# integratedBertha.net
KiCad netlist of a schematic drawn in EAGLE
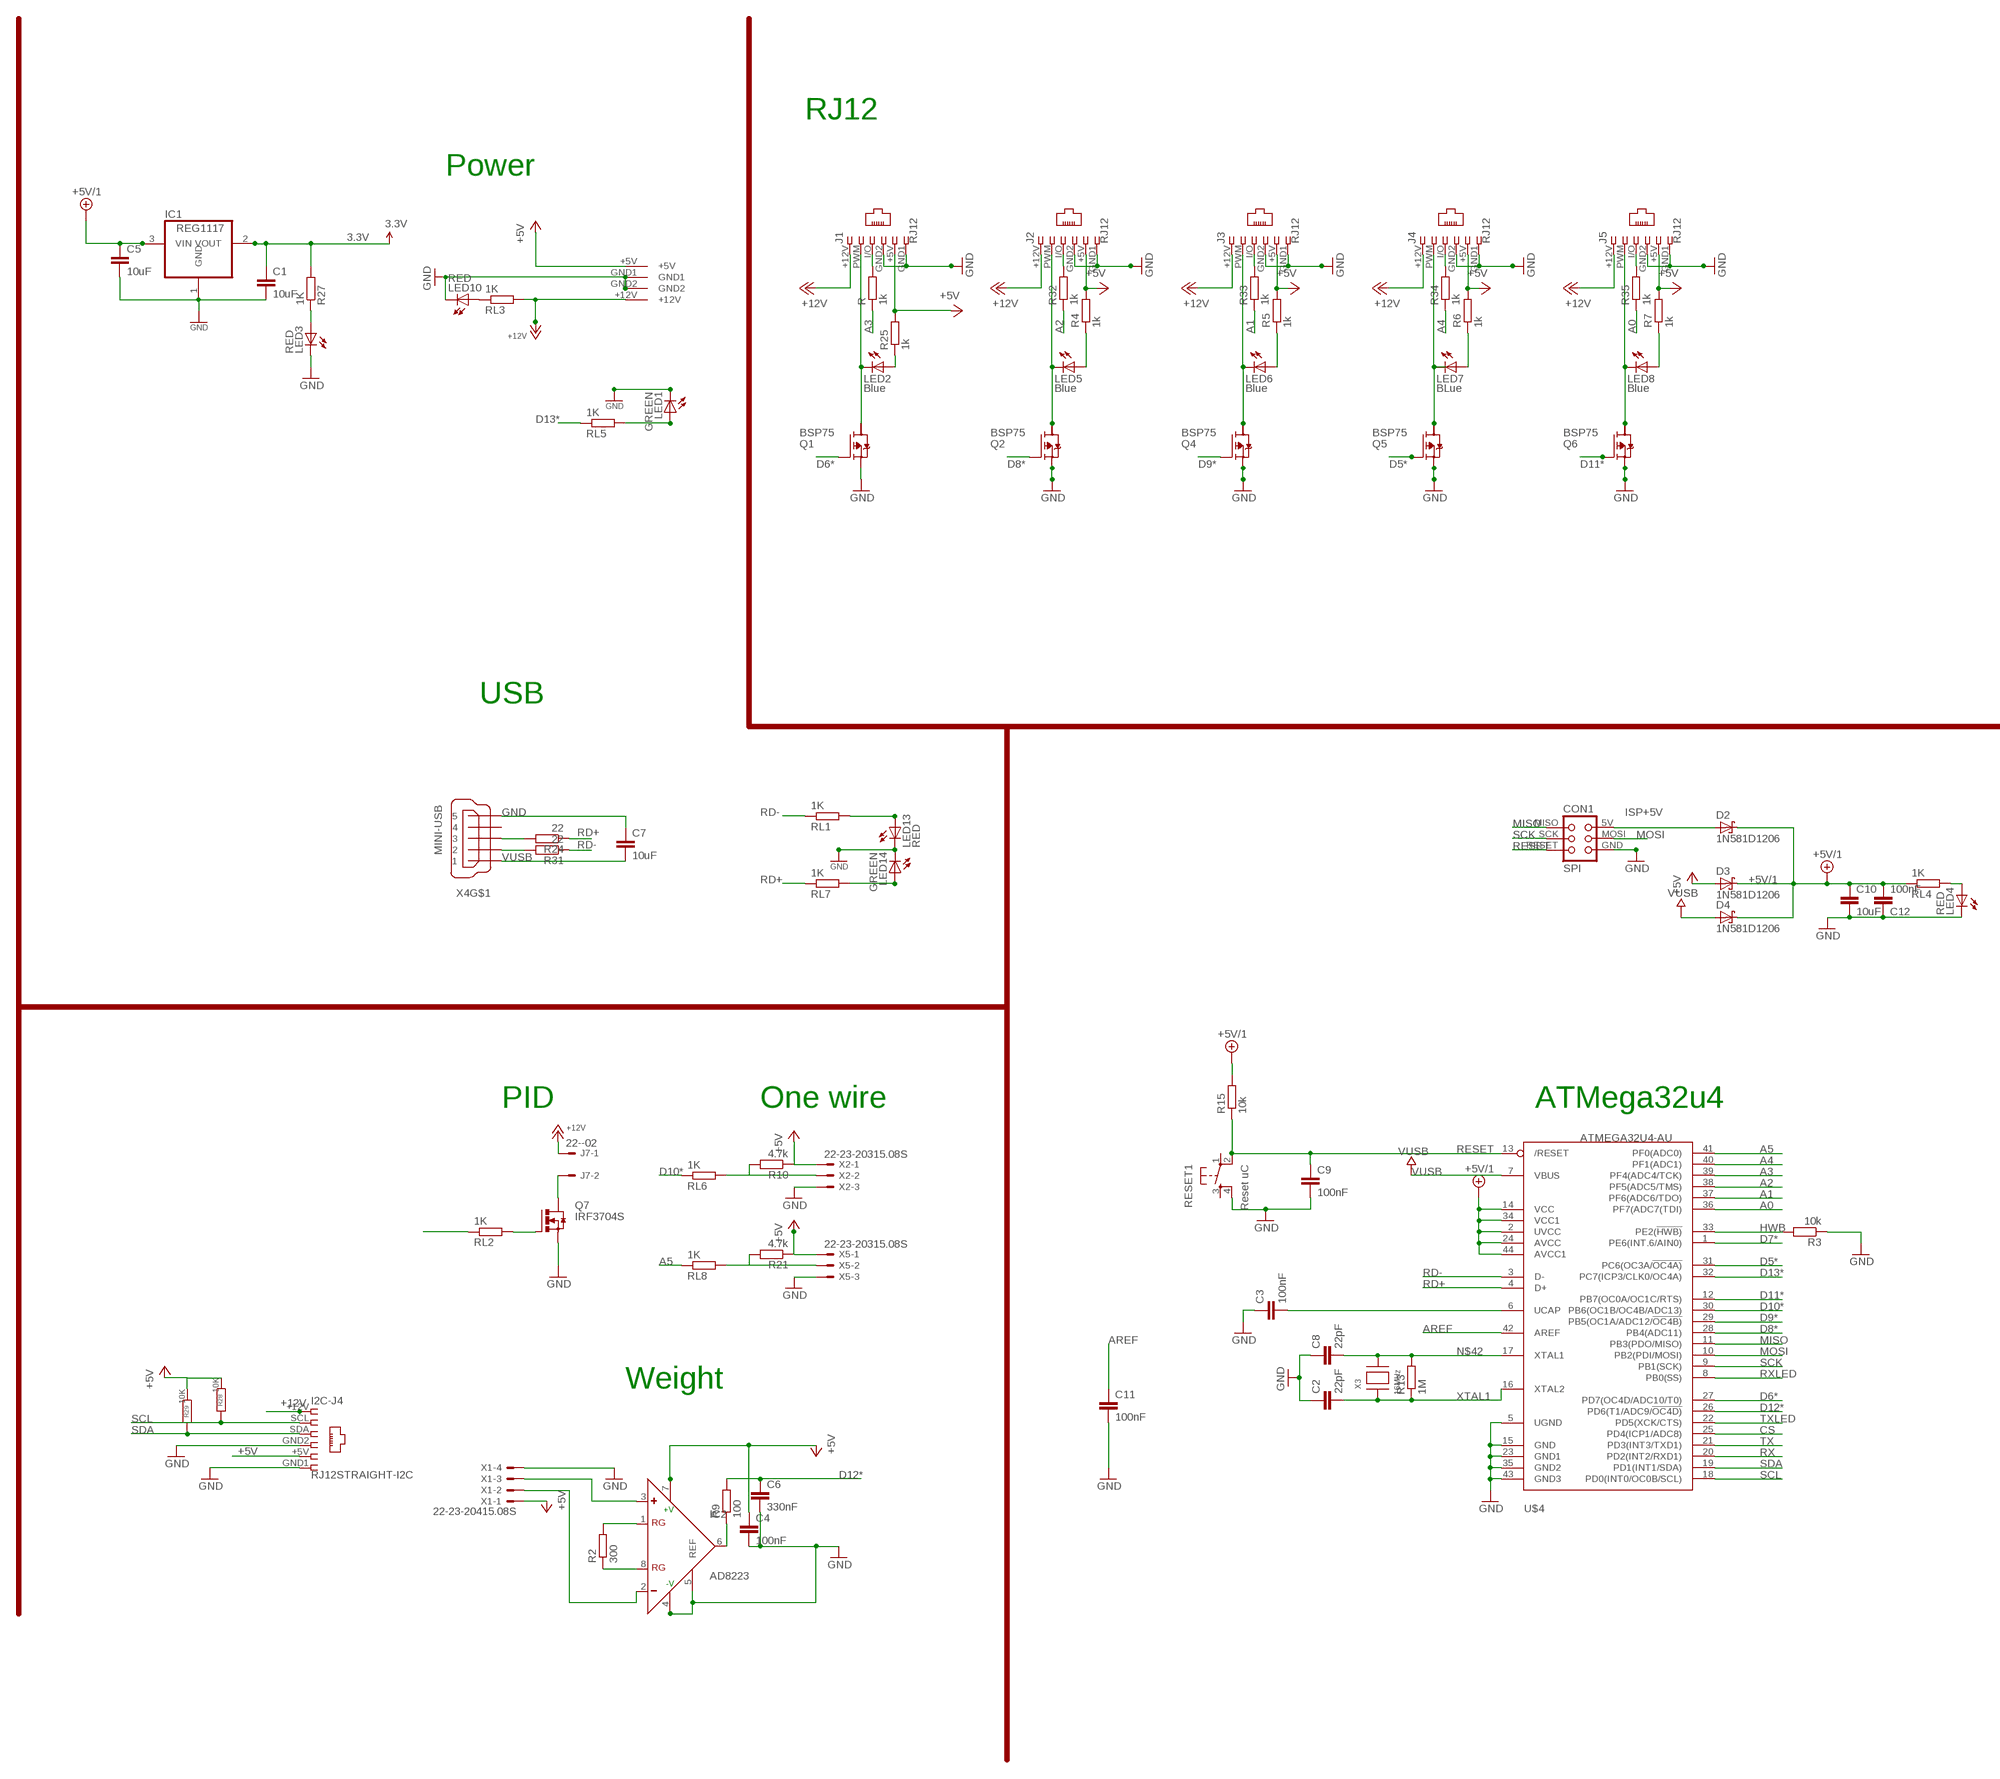
[diagram p0: schematic, sheet 1, part 1 of 2]
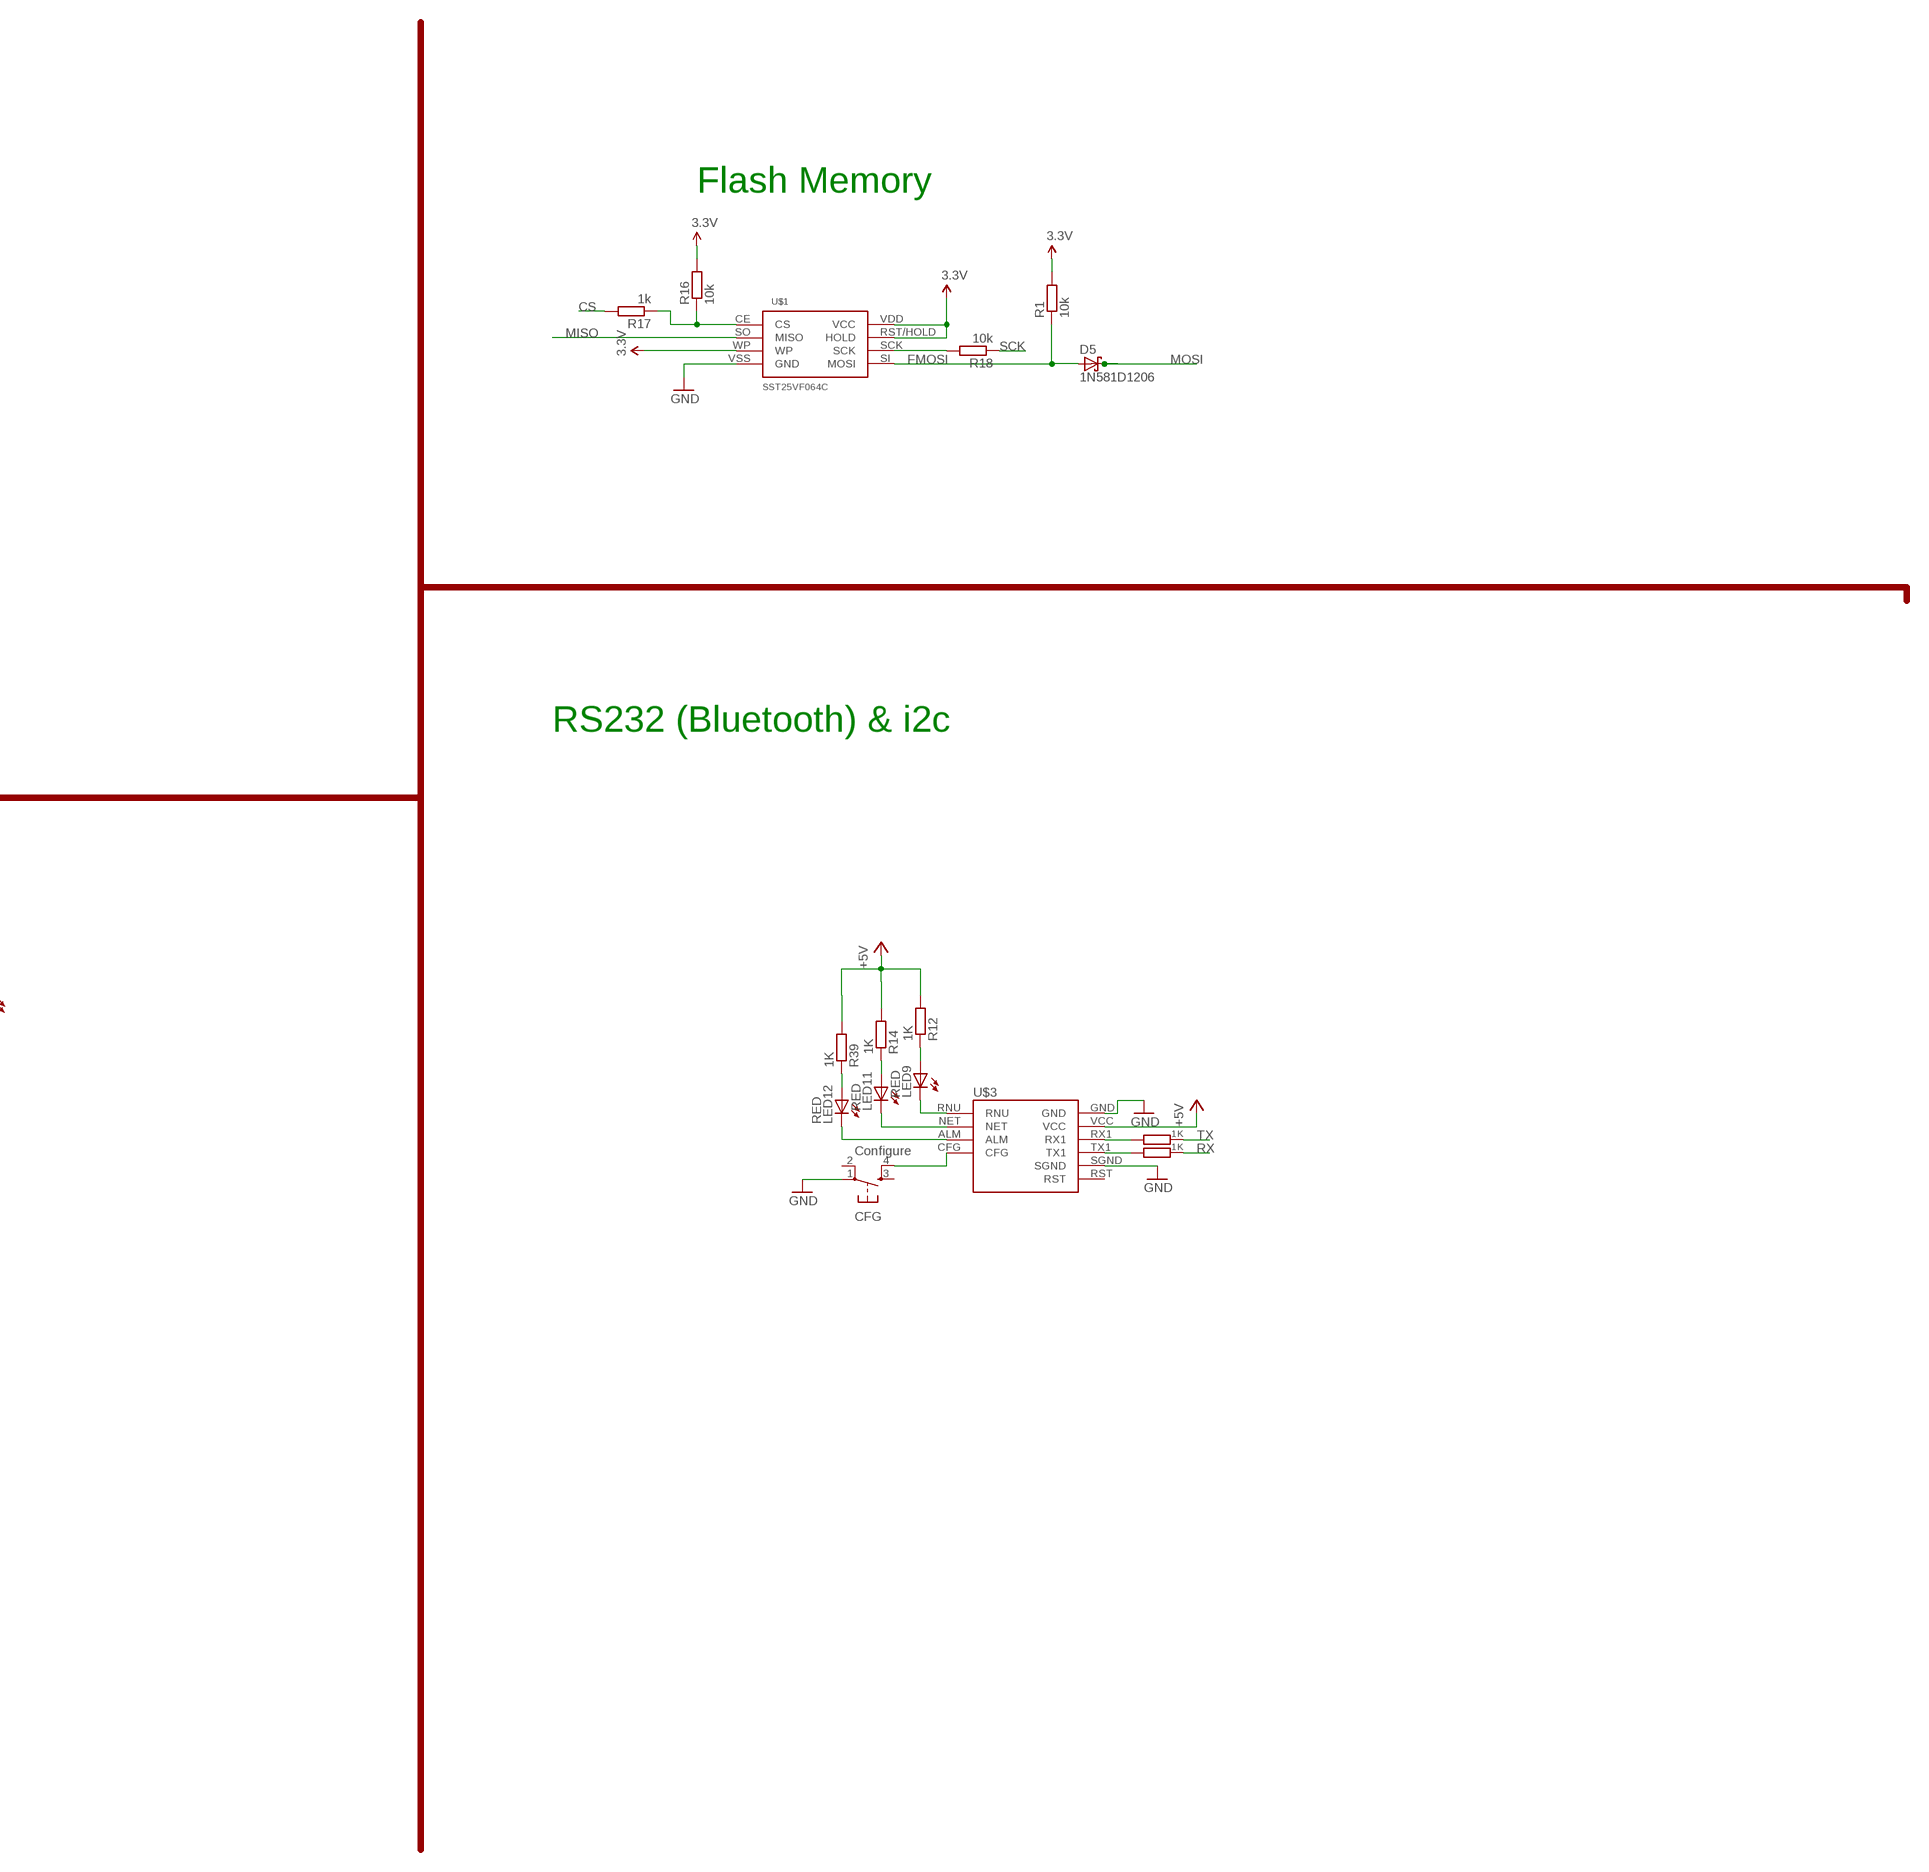
[diagram p1: schematic, sheet 1, part 2 of 2]

(export (version "E")
  (design (tool "Eeschema 10.0.6"))
  (components
    (comp (ref "C1")
      (value "10uF")
      (footprint "eagle-import:C1206")
      (libsource (lib "eagle-import") (part "C-EUC1206"))
    )
    (comp (ref "C2")
      (value "22pF")
      (footprint "eagle-import:C1206")
      (libsource (lib "eagle-import") (part "C-EUC1206"))
    )
    (comp (ref "C3")
      (value "100nF")
      (footprint "eagle-import:C1206")
      (libsource (lib "eagle-import") (part "C-EUC1206"))
    )
    (comp (ref "C4")
      (value "100nF")
      (footprint "eagle-import:C1206")
      (libsource (lib "eagle-import") (part "C-EUC1206"))
    )
    (comp (ref "C5")
      (value "10uF")
      (footprint "eagle-import:C1206")
      (libsource (lib "eagle-import") (part "C-EUC1206"))
    )
    (comp (ref "C6")
      (value "330nF")
      (footprint "eagle-import:C1206")
      (libsource (lib "eagle-import") (part "C-EUC1206"))
    )
    (comp (ref "C7")
      (value "10uF")
      (footprint "eagle-import:C1206")
      (libsource (lib "eagle-import") (part "C-EUC1206"))
    )
    (comp (ref "C8")
      (value "22pF")
      (footprint "eagle-import:C1206")
      (libsource (lib "eagle-import") (part "C-EUC1206"))
    )
    (comp (ref "C9")
      (value "100nF")
      (footprint "eagle-import:C1206")
      (libsource (lib "eagle-import") (part "C-EUC1206"))
    )
    (comp (ref "C10")
      (value "10uF")
      (footprint "eagle-import:C1206")
      (libsource (lib "eagle-import") (part "C-EUC1206"))
    )
    (comp (ref "C11")
      (value "100nF")
      (footprint "eagle-import:C1206")
      (libsource (lib "eagle-import") (part "C-EUC1206"))
    )
    (comp (ref "C12")
      (value "100nF")
      (footprint "eagle-import:C1206")
      (libsource (lib "eagle-import") (part "C-EUC1206"))
    )
    (comp (ref "CFG")
      (value "Configure")
      (footprint "eagle-import:TACTILE_SWITCH_SMD")
      (libsource (lib "eagle-import") (part "TAC_SWITCHSMD"))
    )
    (comp (ref "CON1")
      (value "SPI")
      (footprint "eagle-import:TC2030-MCP-NL")
      (libsource (lib "eagle-import") (part "TINYISPT"))
    )
    (comp (ref "D2")
      (value "1N581D1206")
      (footprint "eagle-import:LED-1206")
      (libsource (lib "eagle-import") (part "1N581D1206"))
    )
    (comp (ref "D3")
      (value "1N581D1206")
      (footprint "eagle-import:LED-1206")
      (libsource (lib "eagle-import") (part "1N581D1206"))
    )
    (comp (ref "D4")
      (value "1N581D1206")
      (footprint "eagle-import:LED-1206")
      (libsource (lib "eagle-import") (part "1N581D1206"))
    )
    (comp (ref "D5")
      (value "1N581D1206")
      (footprint "eagle-import:LED-1206")
      (libsource (lib "eagle-import") (part "1N581D1206"))
    )
    (comp (ref "I2C-J4")
      (value "RJ12STRAIGHT-I2C")
      (footprint "eagle-import:RJ12-STRAIGHT-I2C")
      (libsource (lib "eagle-import") (part "RJ12STRAIGHT-I2C"))
    )
    (comp (ref "IC1")
      (value "REG1117")
      (footprint "eagle-import:SOT223")
      (libsource (lib "eagle-import") (part "REG1117"))
    )
    (comp (ref "IC2")
      (value "AD8223")
      (footprint "eagle-import:SO8")
      (fields (field (name "MPN") "AD620AR"))
      (libsource (lib "eagle-import") (part "AD620R"))
    )
    (comp (ref "J1")
      (value "RJ12")
      (footprint "eagle-import:RJ12-STRAIGHT")
      (libsource (lib "eagle-import") (part "RJ12STRAIGHT"))
    )
    (comp (ref "J2")
      (value "RJ12")
      (footprint "eagle-import:RJ12-STRAIGHT")
      (libsource (lib "eagle-import") (part "RJ12STRAIGHT"))
    )
    (comp (ref "J3")
      (value "RJ12")
      (footprint "eagle-import:RJ12-STRAIGHT")
      (libsource (lib "eagle-import") (part "RJ12STRAIGHT"))
    )
    (comp (ref "J4")
      (value "RJ12")
      (footprint "eagle-import:RJ12-STRAIGHT")
      (libsource (lib "eagle-import") (part "RJ12STRAIGHT"))
    )
    (comp (ref "J5")
      (value "RJ12")
      (footprint "eagle-import:RJ12-STRAIGHT")
      (libsource (lib "eagle-import") (part "RJ12STRAIGHT"))
    )
    (comp (ref "J7")
      (value "22--02")
      (footprint "eagle-import:2-PIN-5.08S")
      (libsource (lib "eagle-import") (part "22-?-02"))
    )
    (comp (ref "LED1")
      (value "GREEN")
      (footprint "eagle-import:CHIPLED_1206")
      (libsource (lib "eagle-import") (part "LEDCHIPLED_1206"))
    )
    (comp (ref "LED2")
      (value "Blue")
      (footprint "eagle-import:CHIPLED_1206")
      (libsource (lib "eagle-import") (part "LEDCHIPLED_1206"))
    )
    (comp (ref "LED3")
      (value "RED")
      (footprint "eagle-import:CHIPLED_1206")
      (libsource (lib "eagle-import") (part "LEDCHIPLED_1206"))
    )
    (comp (ref "LED4")
      (value "RED")
      (footprint "eagle-import:CHIPLED_1206")
      (libsource (lib "eagle-import") (part "LEDCHIPLED_1206"))
    )
    (comp (ref "LED5")
      (value "Blue")
      (footprint "eagle-import:CHIPLED_1206")
      (libsource (lib "eagle-import") (part "LEDCHIPLED_1206"))
    )
    (comp (ref "LED6")
      (value "Blue")
      (footprint "eagle-import:CHIPLED_1206")
      (libsource (lib "eagle-import") (part "LEDCHIPLED_1206"))
    )
    (comp (ref "LED7")
      (value "BLue")
      (footprint "eagle-import:CHIPLED_1206")
      (libsource (lib "eagle-import") (part "LEDCHIPLED_1206"))
    )
    (comp (ref "LED8")
      (value "Blue")
      (footprint "eagle-import:CHIPLED_1206")
      (libsource (lib "eagle-import") (part "LEDCHIPLED_1206"))
    )
    (comp (ref "LED9")
      (value "RED")
      (footprint "eagle-import:CHIPLED_1206")
      (libsource (lib "eagle-import") (part "LEDCHIPLED_1206"))
    )
    (comp (ref "LED10")
      (value "RED")
      (footprint "eagle-import:CHIPLED_1206")
      (libsource (lib "eagle-import") (part "LEDCHIPLED_1206"))
    )
    (comp (ref "LED11")
      (value "RED")
      (footprint "eagle-import:CHIPLED_1206")
      (libsource (lib "eagle-import") (part "LEDCHIPLED_1206"))
    )
    (comp (ref "LED12")
      (value "RED")
      (footprint "eagle-import:CHIPLED_1206")
      (libsource (lib "eagle-import") (part "LEDCHIPLED_1206"))
    )
    (comp (ref "LED13")
      (value "RED")
      (footprint "eagle-import:CHIPLED_1206")
      (libsource (lib "eagle-import") (part "LEDCHIPLED_1206"))
    )
    (comp (ref "LED14")
      (value "GREEN")
      (footprint "eagle-import:CHIPLED_1206")
      (libsource (lib "eagle-import") (part "LEDCHIPLED_1206"))
    )
    (comp (ref "Q1")
      (value "BSP75")
      (footprint "eagle-import:PG-SOT-223")
      (libsource (lib "eagle-import") (part "BSP613P"))
    )
    (comp (ref "Q2")
      (value "BSP75")
      (footprint "eagle-import:PG-SOT-223")
      (libsource (lib "eagle-import") (part "BSP613P"))
    )
    (comp (ref "Q4")
      (value "BSP75")
      (footprint "eagle-import:PG-SOT-223")
      (libsource (lib "eagle-import") (part "BSP613P"))
    )
    (comp (ref "Q5")
      (value "BSP75")
      (footprint "eagle-import:PG-SOT-223")
      (libsource (lib "eagle-import") (part "BSP613P"))
    )
    (comp (ref "Q6")
      (value "BSP75")
      (footprint "eagle-import:PG-SOT-223")
      (libsource (lib "eagle-import") (part "BSP613P"))
    )
    (comp (ref "Q7")
      (value "IRF3704S")
      (footprint "eagle-import:D2PACK")
      (libsource (lib "eagle-import") (part "IRF3704S"))
    )
    (comp (ref "R")
      (value "1k")
      (footprint "eagle-import:R0805")
      (libsource (lib "eagle-import") (part "R-EU_R0805"))
    )
    (comp (ref "R1")
      (value "10k")
      (footprint "eagle-import:R0805")
      (libsource (lib "eagle-import") (part "R-EU_R0805"))
    )
    (comp (ref "R2")
      (value "300")
      (footprint "eagle-import:R1206")
      (libsource (lib "eagle-import") (part "resistor_R-EU_R1206"))
    )
    (comp (ref "R3")
      (value "10k")
      (footprint "eagle-import:M0805")
      (libsource (lib "eagle-import") (part "resistor_R-EU_M0805"))
    )
    (comp (ref "R4")
      (value "1k")
      (footprint "eagle-import:R0805")
      (libsource (lib "eagle-import") (part "R-EU_R0805"))
    )
    (comp (ref "R5")
      (value "1k")
      (footprint "eagle-import:R0805")
      (libsource (lib "eagle-import") (part "R-EU_R0805"))
    )
    (comp (ref "R6")
      (value "1k")
      (footprint "eagle-import:R0805")
      (libsource (lib "eagle-import") (part "R-EU_R0805"))
    )
    (comp (ref "R7")
      (value "1k")
      (footprint "eagle-import:R0805")
      (libsource (lib "eagle-import") (part "R-EU_R0805"))
    )
    (comp (ref "R8")
      (value "1K")
      (footprint "eagle-import:R0805")
      (libsource (lib "eagle-import") (part "R-EU_R0805"))
    )
    (comp (ref "R9")
      (value "100")
      (footprint "eagle-import:R1206")
      (libsource (lib "eagle-import") (part "resistor_R-EU_R1206"))
    )
    (comp (ref "R10")
      (value "4.7k")
      (footprint "eagle-import:R1206")
      (libsource (lib "eagle-import") (part "resistor_R-EU_R1206"))
    )
    (comp (ref "R11")
      (value "1K")
      (footprint "eagle-import:R0805")
      (libsource (lib "eagle-import") (part "R-EU_R0805"))
    )
    (comp (ref "R12")
      (value "1K")
      (footprint "eagle-import:R0805")
      (libsource (lib "eagle-import") (part "R-EU_R0805"))
    )
    (comp (ref "R13")
      (value "1M")
      (footprint "eagle-import:R1206")
      (libsource (lib "eagle-import") (part "R-EU_R1206"))
    )
    (comp (ref "R14")
      (value "1K")
      (footprint "eagle-import:R0805")
      (libsource (lib "eagle-import") (part "R-EU_R0805"))
    )
    (comp (ref "R15")
      (value "10k")
      (footprint "eagle-import:M0805")
      (libsource (lib "eagle-import") (part "resistor_R-EU_M0805"))
    )
    (comp (ref "R16")
      (value "10k")
      (footprint "eagle-import:R0805")
      (libsource (lib "eagle-import") (part "R-EU_R0805"))
    )
    (comp (ref "R17")
      (value "1k")
      (footprint "eagle-import:R0805")
      (libsource (lib "eagle-import") (part "R-EU_R0805"))
    )
    (comp (ref "R18")
      (value "10k")
      (footprint "eagle-import:R0805")
      (libsource (lib "eagle-import") (part "R-EU_R0805"))
    )
    (comp (ref "R21")
      (value "4.7k")
      (footprint "eagle-import:R1206")
      (libsource (lib "eagle-import") (part "resistor_R-EU_R1206"))
    )
    (comp (ref "R24")
      (value "22")
      (footprint "eagle-import:M1206")
      (libsource (lib "eagle-import") (part "resistor_R-EU_M1206"))
    )
    (comp (ref "R25")
      (value "1k")
      (footprint "eagle-import:R0805")
      (libsource (lib "eagle-import") (part "R-EU_R0805"))
    )
    (comp (ref "R27")
      (value "1K")
      (footprint "eagle-import:R0805")
      (libsource (lib "eagle-import") (part "R-EU_R0805"))
    )
    (comp (ref "R28")
      (value "10K")
      (footprint "eagle-import:M0805")
      (libsource (lib "eagle-import") (part "resistor_R-EU_M0805"))
    )
    (comp (ref "R29")
      (value "10K")
      (footprint "eagle-import:M0805")
      (libsource (lib "eagle-import") (part "resistor_R-EU_M0805"))
    )
    (comp (ref "R31")
      (value "22")
      (footprint "eagle-import:M1206")
      (libsource (lib "eagle-import") (part "resistor_R-EU_M1206"))
    )
    (comp (ref "R32")
      (value "1k")
      (footprint "eagle-import:R0805")
      (libsource (lib "eagle-import") (part "R-EU_R0805"))
    )
    (comp (ref "R33")
      (value "1k")
      (footprint "eagle-import:R0805")
      (libsource (lib "eagle-import") (part "R-EU_R0805"))
    )
    (comp (ref "R34")
      (value "1k")
      (footprint "eagle-import:R0805")
      (libsource (lib "eagle-import") (part "R-EU_R0805"))
    )
    (comp (ref "R35")
      (value "1k")
      (footprint "eagle-import:R0805")
      (libsource (lib "eagle-import") (part "R-EU_R0805"))
    )
    (comp (ref "R39")
      (value "1K")
      (footprint "eagle-import:R0805")
      (libsource (lib "eagle-import") (part "R-EU_R0805"))
    )
    (comp (ref "RESET1")
      (value "Reset uC")
      (footprint "eagle-import:TACTILE_SWITCH_SMD")
      (libsource (lib "eagle-import") (part "TAC_SWITCHSMD"))
    )
    (comp (ref "RL1")
      (value "1K")
      (footprint "eagle-import:R0805")
      (libsource (lib "eagle-import") (part "R-EU_R0805"))
    )
    (comp (ref "RL2")
      (value "1K")
      (footprint "eagle-import:R0805")
      (libsource (lib "eagle-import") (part "R-EU_R0805"))
    )
    (comp (ref "RL3")
      (value "1K")
      (footprint "eagle-import:R0805")
      (libsource (lib "eagle-import") (part "R-EU_R0805"))
    )
    (comp (ref "RL4")
      (value "1K")
      (footprint "eagle-import:R0805")
      (libsource (lib "eagle-import") (part "resistor_R-EU_R0805"))
    )
    (comp (ref "RL5")
      (value "1K")
      (footprint "eagle-import:R0805")
      (libsource (lib "eagle-import") (part "R-EU_R0805"))
    )
    (comp (ref "RL6")
      (value "1K")
      (footprint "eagle-import:R0805")
      (libsource (lib "eagle-import") (part "R-EU_R0805"))
    )
    (comp (ref "RL7")
      (value "1K")
      (footprint "eagle-import:R0805")
      (libsource (lib "eagle-import") (part "R-EU_R0805"))
    )
    (comp (ref "RL8")
      (value "1K")
      (footprint "eagle-import:R0805")
      (libsource (lib "eagle-import") (part "R-EU_R0805"))
    )
    (comp (ref "U$1")
      (value "SST25VF064C")
      (footprint "eagle-import:SOIC_8-LEAD")
      (libsource (lib "eagle-import") (part "SST25VF064C"))
    )
    (comp (ref "U$3")
      (value "SZ05-ZIGBEE")
      (footprint "eagle-import:SZ05-ZIGBEE")
      (libsource (lib "eagle-import") (part "SZ05-ZIGBEE"))
    )
    (comp (ref "U$4")
      (value "ATMEGA32U4-AU")
      (footprint "eagle-import:TQFP44")
      (libsource (lib "eagle-import") (part "ATMEGA32U4-AU"))
    )
    (comp (ref "U$6")
      (value "KPJX-4S-S")
      (footprint "eagle-import:KPJX-4S-S")
      (libsource (lib "eagle-import") (part "KPJX-4S-S"))
    )
    (comp (ref "X1")
      (value "22-23-20415.08S")
      (footprint "eagle-import:4-PIN-5.08S")
      (libsource (lib "eagle-import") (part "22-23-20415.08S"))
    )
    (comp (ref "X2")
      (value "22-23-20315.08S")
      (footprint "eagle-import:3-PIN-5.08S")
      (libsource (lib "eagle-import") (part "22-23-20315.08S"))
    )
    (comp (ref "X3")
      (value "16MHz")
      (footprint "eagle-import:NX6035")
      (libsource (lib "eagle-import") (part "XTALNX6035"))
    )
    (comp (ref "X4")
      (value "MINI-USB")
      (footprint "eagle-import:32005-201")
      (libsource (lib "eagle-import") (part "MINI-USB-SCHIELD-32005-201"))
    )
    (comp (ref "X5")
      (value "22-23-20315.08S")
      (footprint "eagle-import:3-PIN-5.08S")
      (libsource (lib "eagle-import") (part "22-23-20315.08S"))
    )
  )
  (nets
    (net (code "1") (name "+5V") (class "Default")
      (node (ref "C4") (pin "1") (pinfunction "1_1") (pintype "passive"))
      (node (ref "D3") (pin "A") (pinfunction "A_A") (pintype "passive"))
      (node (ref "I2C-J4") (pin "+5V") (pinfunction "5_+5V") (pintype "bidirectional"))
      (node (ref "IC2") (pin "7") (pinfunction "+V_7") (pintype "power_in"))
      (node (ref "J1") (pin "+5V") (pinfunction "5_+5V") (pintype "bidirectional"))
      (node (ref "J2") (pin "+5V") (pinfunction "5_+5V") (pintype "bidirectional"))
      (node (ref "J3") (pin "+5V") (pinfunction "5_+5V") (pintype "bidirectional"))
      (node (ref "J4") (pin "+5V") (pinfunction "5_+5V") (pintype "bidirectional"))
      (node (ref "J5") (pin "+5V") (pinfunction "5_+5V") (pintype "bidirectional"))
      (node (ref "R10") (pin "1") (pinfunction "1_1") (pintype "passive"))
      (node (ref "R12") (pin "2") (pinfunction "2_2") (pintype "passive"))
      (node (ref "R14") (pin "2") (pinfunction "2_2") (pintype "passive"))
      (node (ref "R21") (pin "1") (pinfunction "1_1") (pintype "passive"))
      (node (ref "R25") (pin "2") (pinfunction "2_2") (pintype "passive"))
      (node (ref "R28") (pin "1") (pinfunction "1_1") (pintype "passive"))
      (node (ref "R29") (pin "1") (pinfunction "1_1") (pintype "passive"))
      (node (ref "R39") (pin "2") (pinfunction "2_2") (pintype "passive"))
      (node (ref "R4") (pin "2") (pinfunction "2_2") (pintype "passive"))
      (node (ref "R5") (pin "2") (pinfunction "2_2") (pintype "passive"))
      (node (ref "R6") (pin "2") (pinfunction "2_2") (pintype "passive"))
      (node (ref "R7") (pin "2") (pinfunction "2_2") (pintype "passive"))
      (node (ref "U$3") (pin "VCC") (pinfunction "VCC_VCC") (pintype "bidirectional"))
      (node (ref "U$6") (pin "+5V") (pinfunction "+5V_+5V") (pintype "power_in"))
      (node (ref "X1") (pin "1") (pinfunction "S_1") (pintype "passive"))
      (node (ref "X2") (pin "1") (pinfunction "S_1") (pintype "passive"))
      (node (ref "X5") (pin "1") (pinfunction "S_1") (pintype "passive"))
    )
    (net (code "2") (name "+5V{slash}1") (class "Default")
      (node (ref "C10") (pin "1") (pinfunction "1_1") (pintype "passive"))
      (node (ref "C12") (pin "2") (pinfunction "2_2") (pintype "passive"))
      (node (ref "C5") (pin "1") (pinfunction "1_1") (pintype "passive"))
      (node (ref "D2") (pin "C") (pinfunction "C_C") (pintype "passive"))
      (node (ref "D3") (pin "C") (pinfunction "C_C") (pintype "passive"))
      (node (ref "D4") (pin "C") (pinfunction "C_C") (pintype "passive"))
      (node (ref "IC1") (pin "3") (pinfunction "VIN_3") (pintype "input"))
      (node (ref "R15") (pin "2") (pinfunction "2_2") (pintype "passive"))
      (node (ref "RL4") (pin "1") (pinfunction "1_1") (pintype "passive"))
      (node (ref "U$4") (pin "14") (pinfunction "VCC_14") (pintype "bidirectional"))
      (node (ref "U$4") (pin "2") (pinfunction "UVCC_2") (pintype "bidirectional"))
      (node (ref "U$4") (pin "24") (pinfunction "AVCC_24") (pintype "bidirectional"))
      (node (ref "U$4") (pin "34") (pinfunction "VCC1_34") (pintype "bidirectional"))
      (node (ref "U$4") (pin "44") (pinfunction "AVCC1_44") (pintype "bidirectional"))
    )
    (net (code "3") (name "+12V") (class "Default")
      (node (ref "I2C-J4") (pin "+12V") (pinfunction "1_+12V") (pintype "bidirectional"))
      (node (ref "J1") (pin "+12V") (pinfunction "1_+12V") (pintype "bidirectional"))
      (node (ref "J2") (pin "+12V") (pinfunction "1_+12V") (pintype "bidirectional"))
      (node (ref "J3") (pin "+12V") (pinfunction "1_+12V") (pintype "bidirectional"))
      (node (ref "J4") (pin "+12V") (pinfunction "1_+12V") (pintype "bidirectional"))
      (node (ref "J5") (pin "+12V") (pinfunction "1_+12V") (pintype "bidirectional"))
      (node (ref "J7") (pin "1") (pinfunction "S_1") (pintype "passive"))
      (node (ref "RL3") (pin "2") (pinfunction "2_2") (pintype "passive"))
      (node (ref "U$6") (pin "+12V") (pinfunction "+12V_+12V") (pintype "power_in"))
    )
    (net (code "4") (name "/A0") (class "Default")
      (node (ref "R35") (pin "1") (pinfunction "1_1") (pintype "passive"))
      (node (ref "U$4") (pin "36") (pinfunction "PF7(ADC7(TDI)_36") (pintype "bidirectional"))
    )
    (net (code "5") (name "/A1") (class "Default")
      (node (ref "R33") (pin "1") (pinfunction "1_1") (pintype "passive"))
      (node (ref "U$4") (pin "37") (pinfunction "PF6(ADC6/TDO)_37") (pintype "bidirectional"))
    )
    (net (code "6") (name "/A2") (class "Default")
      (node (ref "R32") (pin "1") (pinfunction "1_1") (pintype "passive"))
      (node (ref "U$4") (pin "38") (pinfunction "PF5(ADC5/TMS)_38") (pintype "bidirectional"))
    )
    (net (code "7") (name "/A3") (class "Default")
      (node (ref "R") (pin "1") (pinfunction "1_1") (pintype "passive"))
      (node (ref "U$4") (pin "39") (pinfunction "PF4(ADC4/TCK)_39") (pintype "bidirectional"))
    )
    (net (code "8") (name "/A4") (class "Default")
      (node (ref "R34") (pin "1") (pinfunction "1_1") (pintype "passive"))
      (node (ref "U$4") (pin "40") (pinfunction "PF1(ADC1)_40") (pintype "bidirectional"))
    )
    (net (code "9") (name "/A5") (class "Default")
      (node (ref "RL8") (pin "1") (pinfunction "1_1") (pintype "passive"))
      (node (ref "U$4") (pin "41") (pinfunction "PF0(ADC0)_41") (pintype "bidirectional"))
    )
    (net (code "10") (name "/AREF") (class "Default")
      (node (ref "C11") (pin "1") (pinfunction "1_1") (pintype "passive"))
      (node (ref "U$4") (pin "42") (pinfunction "AREF_42") (pintype "bidirectional"))
    )
    (net (code "11") (name "/CS") (class "Default")
      (node (ref "R17") (pin "2") (pinfunction "2_2") (pintype "passive"))
      (node (ref "U$4") (pin "25") (pinfunction "PD4(ICP1/ADC8)_25") (pintype "bidirectional"))
    )
    (net (code "12") (name "/D5*") (class "Default")
      (node (ref "Q5") (pin "1") (pinfunction "G_1") (pintype "passive"))
      (node (ref "U$4") (pin "31") (pinfunction "PC6(OC3A/~{OC4A})_31") (pintype "bidirectional"))
    )
    (net (code "13") (name "/D6*") (class "Default")
      (node (ref "Q1") (pin "1") (pinfunction "G_1") (pintype "passive"))
      (node (ref "U$4") (pin "27") (pinfunction "PD7(OC4D/ADC10/T0)_27") (pintype "bidirectional"))
    )
    (net (code "14") (name "/D7*") (class "Default")
      (node (ref "RL2") (pin "1") (pinfunction "1_1") (pintype "passive"))
      (node (ref "U$4") (pin "1") (pinfunction "PE6(INT.6/AIN0)_1") (pintype "bidirectional"))
    )
    (net (code "15") (name "/D8*") (class "Default")
      (node (ref "Q2") (pin "1") (pinfunction "G_1") (pintype "passive"))
      (node (ref "U$4") (pin "28") (pinfunction "PB4(ADC11)_28") (pintype "bidirectional"))
    )
    (net (code "16") (name "/D9*") (class "Default")
      (node (ref "Q4") (pin "1") (pinfunction "G_1") (pintype "passive"))
      (node (ref "U$4") (pin "29") (pinfunction "PB5(OC1A/ADC12/~{OC4B})_29") (pintype "bidirectional"))
    )
    (net (code "17") (name "/D10*") (class "Default")
      (node (ref "RL6") (pin "1") (pinfunction "1_1") (pintype "passive"))
      (node (ref "U$4") (pin "30") (pinfunction "PB6(OC1B/OC4B/ADC13)_30") (pintype "bidirectional"))
    )
    (net (code "18") (name "/D11*") (class "Default")
      (node (ref "Q6") (pin "1") (pinfunction "G_1") (pintype "passive"))
      (node (ref "U$4") (pin "12") (pinfunction "PB7(OC0A/OC1C/RTS)_12") (pintype "bidirectional"))
    )
    (net (code "19") (name "/D12*") (class "Default")
      (node (ref "C6") (pin "1") (pinfunction "1_1") (pintype "passive"))
      (node (ref "R9") (pin "2") (pinfunction "2_2") (pintype "passive"))
      (node (ref "U$4") (pin "26") (pinfunction "PD6(T1/ADC9/~{OC4D})_26") (pintype "bidirectional"))
    )
    (net (code "20") (name "/D13*") (class "Default")
      (node (ref "RL5") (pin "1") (pinfunction "1_1") (pintype "passive"))
      (node (ref "U$4") (pin "32") (pinfunction "PC7(ICP3/CLK0/OC4A)_32") (pintype "bidirectional"))
    )
    (net (code "21") (name "/FMOSI") (class "Default")
      (node (ref "D5") (pin "A") (pinfunction "A_A") (pintype "passive"))
      (node (ref "R1") (pin "1") (pinfunction "1_1") (pintype "passive"))
      (node (ref "U$1") (pin "SI") (pinfunction "MOSI_SI") (pintype "bidirectional"))
    )
    (net (code "22") (name "/HWB") (class "Default")
      (node (ref "R3") (pin "2") (pinfunction "2_2") (pintype "passive"))
      (node (ref "U$4") (pin "33") (pinfunction "PE2(~{HWB})_33") (pintype "bidirectional"))
    )
    (net (code "23") (name "/ISP+5V") (class "Default")
      (node (ref "CON1") (pin "5V") (pinfunction "VCC_5V") (pintype "passive"))
      (node (ref "D2") (pin "A") (pinfunction "A_A") (pintype "passive"))
    )
    (net (code "24") (name "/MISO") (class "Default")
      (node (ref "CON1") (pin "MISO") (pinfunction "MISO_MISO") (pintype "passive"))
      (node (ref "U$1") (pin "SO") (pinfunction "MISO_SO") (pintype "bidirectional"))
      (node (ref "U$4") (pin "11") (pinfunction "PB3(PDO/MISO)_11") (pintype "bidirectional"))
    )
    (net (code "25") (name "/MOSI") (class "Default")
      (node (ref "CON1") (pin "MOSI") (pinfunction "MOSI_MOSI") (pintype "passive"))
      (node (ref "D5") (pin "C") (pinfunction "C_C") (pintype "passive"))
      (node (ref "U$4") (pin "10") (pinfunction "PB2(PDI/MOSI)_10") (pintype "bidirectional"))
    )
    (net (code "26") (name "/N$42") (class "Default")
      (node (ref "C8") (pin "2") (pinfunction "2_2") (pintype "passive"))
      (node (ref "R13") (pin "2") (pinfunction "2_2") (pintype "passive"))
      (node (ref "U$4") (pin "17") (pinfunction "XTAL1_17") (pintype "bidirectional"))
      (node (ref "X3") (pin "P$2") (pinfunction "P$2_P$2") (pintype "bidirectional"))
    )
    (net (code "27") (name "/RD+") (class "Default")
      (node (ref "R24") (pin "1") (pinfunction "1_1") (pintype "passive"))
      (node (ref "RL7") (pin "1") (pinfunction "1_1") (pintype "passive"))
      (node (ref "U$4") (pin "4") (pinfunction "D+_4") (pintype "bidirectional"))
    )
    (net (code "28") (name "/RD-") (class "Default")
      (node (ref "R31") (pin "1") (pinfunction "1_1") (pintype "passive"))
      (node (ref "RL1") (pin "1") (pinfunction "1_1") (pintype "passive"))
      (node (ref "U$4") (pin "3") (pinfunction "D-_3") (pintype "bidirectional"))
    )
    (net (code "29") (name "/RESET") (class "Default")
      (node (ref "C9") (pin "1") (pinfunction "1_1") (pintype "passive"))
      (node (ref "CON1") (pin "RESET") (pinfunction "RESET_RESET") (pintype "passive"))
      (node (ref "R15") (pin "1") (pinfunction "1_1") (pintype "passive"))
      (node (ref "RESET1") (pin "2") (pinfunction "2_2") (pintype "passive"))
      (node (ref "U$4") (pin "13") (pinfunction "/RESET_13") (pintype "bidirectional"))
    )
    (net (code "30") (name "/RX") (class "Default")
      (node (ref "R8") (pin "1") (pinfunction "1_1") (pintype "passive"))
      (node (ref "U$4") (pin "20") (pinfunction "PD2(INT2/RXD1)_20") (pintype "bidirectional"))
    )
    (net (code "31") (name "/RXLED") (class "Default")
      (node (ref "U$4") (pin "8") (pinfunction "PB0(SS)_8") (pintype "bidirectional"))
    )
    (net (code "32") (name "/SCK") (class "Default")
      (node (ref "CON1") (pin "SCK") (pinfunction "SCK_SCK") (pintype "passive"))
      (node (ref "R18") (pin "1") (pinfunction "1_1") (pintype "passive"))
      (node (ref "U$4") (pin "9") (pinfunction "PB1(SCK)_9") (pintype "bidirectional"))
    )
    (net (code "33") (name "/SCL") (class "Default")
      (node (ref "I2C-J4") (pin "SCL") (pinfunction "2_SCL") (pintype "bidirectional"))
      (node (ref "R28") (pin "2") (pinfunction "2_2") (pintype "passive"))
      (node (ref "U$4") (pin "18") (pinfunction "PD0(INT0/OC0B/SCL)_18") (pintype "bidirectional"))
    )
    (net (code "34") (name "/SDA") (class "Default")
      (node (ref "I2C-J4") (pin "SDA") (pinfunction "3_SDA") (pintype "bidirectional"))
      (node (ref "R29") (pin "2") (pinfunction "2_2") (pintype "passive"))
      (node (ref "U$4") (pin "19") (pinfunction "PD1(INT1/SDA)_19") (pintype "bidirectional"))
    )
    (net (code "35") (name "/TX") (class "Default")
      (node (ref "R11") (pin "1") (pinfunction "1_1") (pintype "passive"))
      (node (ref "U$4") (pin "21") (pinfunction "PD3(INT3/TXD1)_21") (pintype "bidirectional"))
    )
    (net (code "36") (name "/TXLED") (class "Default")
      (node (ref "U$4") (pin "22") (pinfunction "PD5(XCK/CTS)_22") (pintype "bidirectional"))
    )
    (net (code "37") (name "/XTAL1") (class "Default")
      (node (ref "C2") (pin "2") (pinfunction "2_2") (pintype "passive"))
      (node (ref "R13") (pin "1") (pinfunction "1_1") (pintype "passive"))
      (node (ref "U$4") (pin "16") (pinfunction "XTAL2_16") (pintype "bidirectional"))
      (node (ref "X3") (pin "P$1") (pinfunction "P$1_P$1") (pintype "bidirectional"))
    )
    (net (code "38") (name "3.3V") (class "Default")
      (node (ref "C1") (pin "1") (pinfunction "1_1") (pintype "passive"))
      (node (ref "IC1") (pin "2") (pinfunction "VOUT_2") (pintype "output"))
      (node (ref "R1") (pin "2") (pinfunction "2_2") (pintype "passive"))
      (node (ref "R16") (pin "2") (pinfunction "2_2") (pintype "passive"))
      (node (ref "R27") (pin "2") (pinfunction "2_2") (pintype "passive"))
      (node (ref "U$1") (pin "RST/HOLD") (pinfunction "HOLD_RST/HOLD") (pintype "bidirectional"))
      (node (ref "U$1") (pin "VDD") (pinfunction "VCC_VDD") (pintype "bidirectional"))
      (node (ref "U$1") (pin "WP") (pinfunction "WP_WP") (pintype "bidirectional"))
    )
    (net (code "39") (name "GND") (class "Default")
      (node (ref "C1") (pin "2") (pinfunction "2_2") (pintype "passive"))
      (node (ref "C10") (pin "2") (pinfunction "2_2") (pintype "passive"))
      (node (ref "C11") (pin "2") (pinfunction "2_2") (pintype "passive"))
      (node (ref "C12") (pin "1") (pinfunction "1_1") (pintype "passive"))
      (node (ref "C2") (pin "1") (pinfunction "1_1") (pintype "passive"))
      (node (ref "C3") (pin "1") (pinfunction "1_1") (pintype "passive"))
      (node (ref "C4") (pin "2") (pinfunction "2_2") (pintype "passive"))
      (node (ref "C5") (pin "2") (pinfunction "2_2") (pintype "passive"))
      (node (ref "C6") (pin "2") (pinfunction "2_2") (pintype "passive"))
      (node (ref "C7") (pin "1") (pinfunction "1_1") (pintype "passive"))
      (node (ref "C8") (pin "1") (pinfunction "1_1") (pintype "passive"))
      (node (ref "C9") (pin "2") (pinfunction "2_2") (pintype "passive"))
      (node (ref "CFG") (pin "1") (pinfunction "1_1") (pintype "passive"))
      (node (ref "CON1") (pin "GND") (pinfunction "GND_GND") (pintype "passive"))
      (node (ref "I2C-J4") (pin "GND1") (pinfunction "6_GND1") (pintype "bidirectional"))
      (node (ref "I2C-J4") (pin "GND2") (pinfunction "4_GND2") (pintype "bidirectional"))
      (node (ref "IC1") (pin "1") (pinfunction "GND_1") (pintype "power_in"))
      (node (ref "IC2") (pin "4") (pinfunction "-V_4") (pintype "power_in"))
      (node (ref "IC2") (pin "5") (pinfunction "REF_5") (pintype "passive"))
      (node (ref "J1") (pin "GND1") (pinfunction "6_GND1") (pintype "bidirectional"))
      (node (ref "J1") (pin "GND2") (pinfunction "4_GND2") (pintype "bidirectional"))
      (node (ref "J2") (pin "GND1") (pinfunction "6_GND1") (pintype "bidirectional"))
      (node (ref "J2") (pin "GND2") (pinfunction "4_GND2") (pintype "bidirectional"))
      (node (ref "J3") (pin "GND1") (pinfunction "6_GND1") (pintype "bidirectional"))
      (node (ref "J3") (pin "GND2") (pinfunction "4_GND2") (pintype "bidirectional"))
      (node (ref "J4") (pin "GND1") (pinfunction "6_GND1") (pintype "bidirectional"))
      (node (ref "J4") (pin "GND2") (pinfunction "4_GND2") (pintype "bidirectional"))
      (node (ref "J5") (pin "GND1") (pinfunction "6_GND1") (pintype "bidirectional"))
      (node (ref "J5") (pin "GND2") (pinfunction "4_GND2") (pintype "bidirectional"))
      (node (ref "LED1") (pin "C") (pinfunction "C_C") (pintype "passive"))
      (node (ref "LED10") (pin "C") (pinfunction "C_C") (pintype "passive"))
      (node (ref "LED13") (pin "C") (pinfunction "C_C") (pintype "passive"))
      (node (ref "LED14") (pin "C") (pinfunction "C_C") (pintype "passive"))
      (node (ref "LED3") (pin "C") (pinfunction "C_C") (pintype "passive"))
      (node (ref "LED4") (pin "C") (pinfunction "C_C") (pintype "passive"))
      (node (ref "Q1") (pin "3") (pinfunction "S_3") (pintype "passive"))
      (node (ref "Q2") (pin "3") (pinfunction "S_3") (pintype "passive"))
      (node (ref "Q4") (pin "3") (pinfunction "S_3") (pintype "passive"))
      (node (ref "Q5") (pin "3") (pinfunction "S_3") (pintype "passive"))
      (node (ref "Q6") (pin "3") (pinfunction "S_3") (pintype "passive"))
      (node (ref "Q7") (pin "3") (pinfunction "S_3") (pintype "passive"))
      (node (ref "R3") (pin "1") (pinfunction "1_1") (pintype "passive"))
      (node (ref "RESET1") (pin "4") (pinfunction "4_4") (pintype "passive"))
      (node (ref "U$1") (pin "VSS") (pinfunction "GND_VSS") (pintype "bidirectional"))
      (node (ref "U$3") (pin "GND") (pinfunction "GND_GND") (pintype "bidirectional"))
      (node (ref "U$3") (pin "SGND") (pinfunction "SGND_SGND") (pintype "bidirectional"))
      (node (ref "U$4") (pin "15") (pinfunction "GND_15") (pintype "bidirectional"))
      (node (ref "U$4") (pin "23") (pinfunction "GND1_23") (pintype "bidirectional"))
      (node (ref "U$4") (pin "35") (pinfunction "GND2_35") (pintype "bidirectional"))
      (node (ref "U$4") (pin "43") (pinfunction "GND3_43") (pintype "bidirectional"))
      (node (ref "U$4") (pin "5") (pinfunction "UGND_5") (pintype "bidirectional"))
      (node (ref "U$6") (pin "GND1") (pinfunction "GND1_GND1") (pintype "input"))
      (node (ref "U$6") (pin "GND2") (pinfunction "GND2_GND2") (pintype "input"))
      (node (ref "X1") (pin "4") (pinfunction "S_4") (pintype "passive"))
      (node (ref "X2") (pin "3") (pinfunction "S_3") (pintype "passive"))
      (node (ref "X4") (pin "5") (pinfunction "5_5") (pintype "passive"))
      (node (ref "X5") (pin "3") (pinfunction "S_3") (pintype "passive"))
    )
    (net (code "40") (name "Net-(CFG-Pad4)") (class "Default")
      (node (ref "CFG") (pin "4") (pinfunction "4_4") (pintype "passive"))
      (node (ref "U$3") (pin "CFG") (pinfunction "CFG_CFG") (pintype "bidirectional"))
    )
    (net (code "41") (name "Net-(IC2-+)") (class "Default")
      (node (ref "IC2") (pin "3") (pinfunction "+_3") (pintype "input"))
      (node (ref "X1") (pin "3") (pinfunction "S_3") (pintype "passive"))
    )
    (net (code "42") (name "Net-(IC2--)") (class "Default")
      (node (ref "IC2") (pin "2") (pinfunction "-_2") (pintype "input"))
      (node (ref "X1") (pin "2") (pinfunction "S_2") (pintype "passive"))
    )
    (net (code "43") (name "Net-(IC2-OUT)") (class "Default")
      (node (ref "IC2") (pin "6") (pinfunction "OUT_6") (pintype "output"))
      (node (ref "R9") (pin "1") (pinfunction "1_1") (pintype "passive"))
    )
    (net (code "44") (name "Net-(IC2-RG-Pad1)") (class "Default")
      (node (ref "IC2") (pin "1") (pinfunction "RG_1") (pintype "passive"))
      (node (ref "R2") (pin "2") (pinfunction "2_2") (pintype "passive"))
    )
    (net (code "45") (name "Net-(IC2-RG-Pad8)") (class "Default")
      (node (ref "IC2") (pin "8") (pinfunction "RG_8") (pintype "passive"))
      (node (ref "R2") (pin "1") (pinfunction "1_1") (pintype "passive"))
    )
    (net (code "46") (name "Net-(J1-2)") (class "Default")
      (node (ref "J1") (pin "PWM") (pinfunction "2_PWM") (pintype "bidirectional"))
      (node (ref "LED2") (pin "C") (pinfunction "C_C") (pintype "passive"))
      (node (ref "Q1") (pin "2") (pinfunction "D_2") (pintype "passive"))
    )
    (net (code "47") (name "Net-(J1-3)") (class "Default")
      (node (ref "J1") (pin "I/O") (pinfunction "3_I/O") (pintype "bidirectional"))
      (node (ref "R") (pin "2") (pinfunction "2_2") (pintype "passive"))
    )
    (net (code "48") (name "Net-(J2-2)") (class "Default")
      (node (ref "J2") (pin "PWM") (pinfunction "2_PWM") (pintype "bidirectional"))
      (node (ref "LED5") (pin "C") (pinfunction "C_C") (pintype "passive"))
      (node (ref "Q2") (pin "2") (pinfunction "D_2") (pintype "passive"))
    )
    (net (code "49") (name "Net-(J2-3)") (class "Default")
      (node (ref "J2") (pin "I/O") (pinfunction "3_I/O") (pintype "bidirectional"))
      (node (ref "R32") (pin "2") (pinfunction "2_2") (pintype "passive"))
    )
    (net (code "50") (name "Net-(J3-2)") (class "Default")
      (node (ref "J3") (pin "PWM") (pinfunction "2_PWM") (pintype "bidirectional"))
      (node (ref "LED6") (pin "C") (pinfunction "C_C") (pintype "passive"))
      (node (ref "Q4") (pin "2") (pinfunction "D_2") (pintype "passive"))
    )
    (net (code "51") (name "Net-(J3-3)") (class "Default")
      (node (ref "J3") (pin "I/O") (pinfunction "3_I/O") (pintype "bidirectional"))
      (node (ref "R33") (pin "2") (pinfunction "2_2") (pintype "passive"))
    )
    (net (code "52") (name "Net-(J4-2)") (class "Default")
      (node (ref "J4") (pin "PWM") (pinfunction "2_PWM") (pintype "bidirectional"))
      (node (ref "LED7") (pin "C") (pinfunction "C_C") (pintype "passive"))
      (node (ref "Q5") (pin "2") (pinfunction "D_2") (pintype "passive"))
    )
    (net (code "53") (name "Net-(J4-3)") (class "Default")
      (node (ref "J4") (pin "I/O") (pinfunction "3_I/O") (pintype "bidirectional"))
      (node (ref "R34") (pin "2") (pinfunction "2_2") (pintype "passive"))
    )
    (net (code "54") (name "Net-(J5-2)") (class "Default")
      (node (ref "J5") (pin "PWM") (pinfunction "2_PWM") (pintype "bidirectional"))
      (node (ref "LED8") (pin "C") (pinfunction "C_C") (pintype "passive"))
      (node (ref "Q6") (pin "2") (pinfunction "D_2") (pintype "passive"))
    )
    (net (code "55") (name "Net-(J5-3)") (class "Default")
      (node (ref "J5") (pin "I/O") (pinfunction "3_I/O") (pintype "bidirectional"))
      (node (ref "R35") (pin "2") (pinfunction "2_2") (pintype "passive"))
    )
    (net (code "56") (name "Net-(J7B-S)") (class "Default")
      (node (ref "J7") (pin "2") (pinfunction "S_2") (pintype "passive"))
      (node (ref "Q7") (pin "2") (pinfunction "D_2") (pintype "passive"))
    )
    (net (code "57") (name "Net-(LED1-PadA)") (class "Default")
      (node (ref "LED1") (pin "A") (pinfunction "A_A") (pintype "passive"))
      (node (ref "RL5") (pin "2") (pinfunction "2_2") (pintype "passive"))
    )
    (net (code "58") (name "Net-(LED2-PadA)") (class "Default")
      (node (ref "LED2") (pin "A") (pinfunction "A_A") (pintype "passive"))
      (node (ref "R25") (pin "1") (pinfunction "1_1") (pintype "passive"))
    )
    (net (code "59") (name "Net-(LED3-PadA)") (class "Default")
      (node (ref "LED3") (pin "A") (pinfunction "A_A") (pintype "passive"))
      (node (ref "R27") (pin "1") (pinfunction "1_1") (pintype "passive"))
    )
    (net (code "60") (name "Net-(LED4-PadA)") (class "Default")
      (node (ref "LED4") (pin "A") (pinfunction "A_A") (pintype "passive"))
      (node (ref "RL4") (pin "2") (pinfunction "2_2") (pintype "passive"))
    )
    (net (code "61") (name "Net-(LED5-PadA)") (class "Default")
      (node (ref "LED5") (pin "A") (pinfunction "A_A") (pintype "passive"))
      (node (ref "R4") (pin "1") (pinfunction "1_1") (pintype "passive"))
    )
    (net (code "62") (name "Net-(LED6-PadA)") (class "Default")
      (node (ref "LED6") (pin "A") (pinfunction "A_A") (pintype "passive"))
      (node (ref "R5") (pin "1") (pinfunction "1_1") (pintype "passive"))
    )
    (net (code "63") (name "Net-(LED7-PadA)") (class "Default")
      (node (ref "LED7") (pin "A") (pinfunction "A_A") (pintype "passive"))
      (node (ref "R6") (pin "1") (pinfunction "1_1") (pintype "passive"))
    )
    (net (code "64") (name "Net-(LED8-PadA)") (class "Default")
      (node (ref "LED8") (pin "A") (pinfunction "A_A") (pintype "passive"))
      (node (ref "R7") (pin "1") (pinfunction "1_1") (pintype "passive"))
    )
    (net (code "65") (name "Net-(LED9-PadA)") (class "Default")
      (node (ref "LED9") (pin "A") (pinfunction "A_A") (pintype "passive"))
      (node (ref "R12") (pin "1") (pinfunction "1_1") (pintype "passive"))
    )
    (net (code "66") (name "Net-(LED9-PadC)") (class "Default")
      (node (ref "LED9") (pin "C") (pinfunction "C_C") (pintype "passive"))
      (node (ref "U$3") (pin "RNU") (pinfunction "RNU_RNU") (pintype "bidirectional"))
    )
    (net (code "67") (name "Net-(LED10-PadA)") (class "Default")
      (node (ref "LED10") (pin "A") (pinfunction "A_A") (pintype "passive"))
      (node (ref "RL3") (pin "1") (pinfunction "1_1") (pintype "passive"))
    )
    (net (code "68") (name "Net-(LED11-PadA)") (class "Default")
      (node (ref "LED11") (pin "A") (pinfunction "A_A") (pintype "passive"))
      (node (ref "R14") (pin "1") (pinfunction "1_1") (pintype "passive"))
    )
    (net (code "69") (name "Net-(LED11-PadC)") (class "Default")
      (node (ref "LED11") (pin "C") (pinfunction "C_C") (pintype "passive"))
      (node (ref "U$3") (pin "NET") (pinfunction "NET_NET") (pintype "bidirectional"))
    )
    (net (code "70") (name "Net-(LED12-PadA)") (class "Default")
      (node (ref "LED12") (pin "A") (pinfunction "A_A") (pintype "passive"))
      (node (ref "R39") (pin "1") (pinfunction "1_1") (pintype "passive"))
    )
    (net (code "71") (name "Net-(LED12-PadC)") (class "Default")
      (node (ref "LED12") (pin "C") (pinfunction "C_C") (pintype "passive"))
      (node (ref "U$3") (pin "ALM") (pinfunction "ALM_ALM") (pintype "bidirectional"))
    )
    (net (code "72") (name "Net-(LED13-PadA)") (class "Default")
      (node (ref "LED13") (pin "A") (pinfunction "A_A") (pintype "passive"))
      (node (ref "RL1") (pin "2") (pinfunction "2_2") (pintype "passive"))
    )
    (net (code "73") (name "Net-(LED14-PadA)") (class "Default")
      (node (ref "LED14") (pin "A") (pinfunction "A_A") (pintype "passive"))
      (node (ref "RL7") (pin "2") (pinfunction "2_2") (pintype "passive"))
    )
    (net (code "74") (name "Net-(Q7-G)") (class "Default")
      (node (ref "Q7") (pin "1") (pinfunction "G_1") (pintype "passive"))
      (node (ref "RL2") (pin "2") (pinfunction "2_2") (pintype "passive"))
    )
    (net (code "75") (name "Net-(R8-Pad2)") (class "Default")
      (node (ref "R8") (pin "2") (pinfunction "2_2") (pintype "passive"))
      (node (ref "U$3") (pin "TX1") (pinfunction "TX1_TX1") (pintype "bidirectional"))
    )
    (net (code "76") (name "Net-(R11-Pad2)") (class "Default")
      (node (ref "R11") (pin "2") (pinfunction "2_2") (pintype "passive"))
      (node (ref "U$3") (pin "RX1") (pinfunction "RX1_RX1") (pintype "bidirectional"))
    )
    (net (code "77") (name "Net-(R18-Pad2)") (class "Default")
      (node (ref "R18") (pin "2") (pinfunction "2_2") (pintype "passive"))
      (node (ref "U$1") (pin "SCK") (pinfunction "SCK_SCK") (pintype "bidirectional"))
    )
    (net (code "78") (name "Net-(R24-Pad2)") (class "Default")
      (node (ref "R24") (pin "2") (pinfunction "2_2") (pintype "passive"))
      (node (ref "X4") (pin "3") (pinfunction "3_3") (pintype "passive"))
    )
    (net (code "79") (name "Net-(R31-Pad2)") (class "Default")
      (node (ref "R31") (pin "2") (pinfunction "2_2") (pintype "passive"))
      (node (ref "X4") (pin "2") (pinfunction "2_2") (pintype "passive"))
    )
    (net (code "80") (name "Net-(U$1-CS)") (class "Default")
      (node (ref "R16") (pin "1") (pinfunction "1_1") (pintype "passive"))
      (node (ref "R17") (pin "1") (pinfunction "1_1") (pintype "passive"))
      (node (ref "U$1") (pin "CE") (pinfunction "CS_CE") (pintype "bidirectional"))
    )
    (net (code "81") (name "Net-(U$4-UCAP)") (class "Default")
      (node (ref "C3") (pin "2") (pinfunction "2_2") (pintype "passive"))
      (node (ref "U$4") (pin "6") (pinfunction "UCAP_6") (pintype "bidirectional"))
    )
    (net (code "82") (name "Net-(X2B-S)") (class "Default")
      (node (ref "R10") (pin "2") (pinfunction "2_2") (pintype "passive"))
      (node (ref "RL6") (pin "2") (pinfunction "2_2") (pintype "passive"))
      (node (ref "X2") (pin "2") (pinfunction "S_2") (pintype "passive"))
    )
    (net (code "83") (name "Net-(X5B-S)") (class "Default")
      (node (ref "R21") (pin "2") (pinfunction "2_2") (pintype "passive"))
      (node (ref "RL8") (pin "2") (pinfunction "2_2") (pintype "passive"))
      (node (ref "X5") (pin "2") (pinfunction "S_2") (pintype "passive"))
    )
    (net (code "84") (name "VUSB") (class "Default")
      (node (ref "C7") (pin "2") (pinfunction "2_2") (pintype "passive"))
      (node (ref "D4") (pin "A") (pinfunction "A_A") (pintype "passive"))
      (node (ref "U$4") (pin "7") (pinfunction "VBUS_7") (pintype "bidirectional"))
      (node (ref "X4") (pin "1") (pinfunction "1_1") (pintype "passive"))
    )
    (net (code "85") (name "unconnected-(CFG-Pad2)") (class "Default")
      (node (ref "CFG") (pin "2") (pinfunction "2_2") (pintype "passive"))
    )
    (net (code "86") (name "unconnected-(CFG-Pad3)") (class "Default")
      (node (ref "CFG") (pin "3") (pinfunction "3_3") (pintype "passive"))
    )
    (net (code "87") (name "unconnected-(Q1-D-Pad4)") (class "Default")
      (node (ref "Q1") (pin "4") (pinfunction "D_4") (pintype "passive"))
    )
    (net (code "88") (name "unconnected-(Q2-D-Pad4)") (class "Default")
      (node (ref "Q2") (pin "4") (pinfunction "D_4") (pintype "passive"))
    )
    (net (code "89") (name "unconnected-(Q4-D-Pad4)") (class "Default")
      (node (ref "Q4") (pin "4") (pinfunction "D_4") (pintype "passive"))
    )
    (net (code "90") (name "unconnected-(Q5-D-Pad4)") (class "Default")
      (node (ref "Q5") (pin "4") (pinfunction "D_4") (pintype "passive"))
    )
    (net (code "91") (name "unconnected-(Q6-D-Pad4)") (class "Default")
      (node (ref "Q6") (pin "4") (pinfunction "D_4") (pintype "passive"))
    )
    (net (code "92") (name "unconnected-(RESET1-Pad1)") (class "Default")
      (node (ref "RESET1") (pin "1") (pinfunction "1_1") (pintype "passive"))
    )
    (net (code "93") (name "unconnected-(RESET1-Pad3)") (class "Default")
      (node (ref "RESET1") (pin "3") (pinfunction "3_3") (pintype "passive"))
    )
    (net (code "94") (name "unconnected-(U$3-PadRST)") (class "Default")
      (node (ref "U$3") (pin "RST") (pinfunction "RST_RST") (pintype "bidirectional"))
    )
    (net (code "95") (name "unconnected-(X4-Pad4)") (class "Default")
      (node (ref "X4") (pin "4") (pinfunction "4_4") (pintype "passive"))
    )
  )
)
